# PIC32_Subsystem.net
KiCad netlist of a schematic drawn in Altium Designer
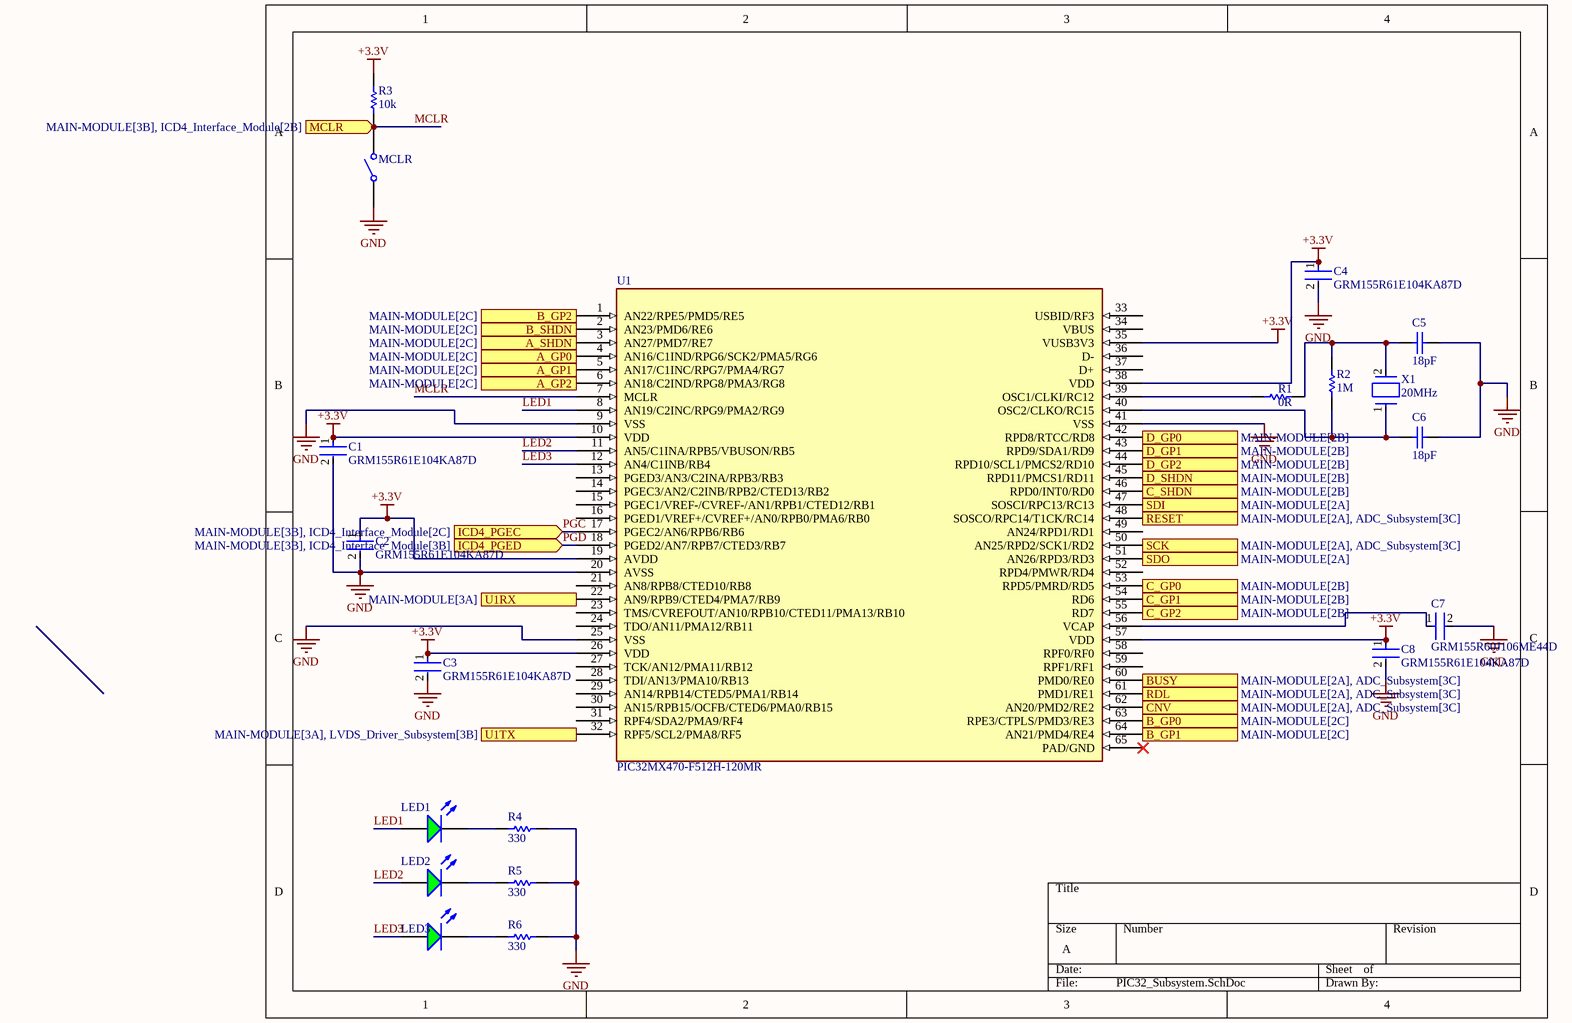
[diagram p0: PIC32_Subsystem.SchDoc]

(export (version "E")
  (design (tool "Eeschema 10.0.6"))
  (components
    (comp (ref "C1")
      (value "GRM155R61E104KA87D")
      (footprint "FP-GRM155-0_05-IPC_A")
      (description "CAP CER 0.1UF 25V X5R 0402")
      (fields (field (name "VOLTAGE") "25V") (field (name "TOLERANCE") "10%"))
      (libsource (lib "Altium Content Vault") (part "11868f565c42a9108669ba33697ecf6"))
    )
    (comp (ref "C2")
      (value "GRM155R61E104KA87D")
      (footprint "FP-GRM155-0_05-IPC_A")
      (description "CAP CER 0.1UF 25V X5R 0402")
      (fields (field (name "VOLTAGE") "25V") (field (name "TOLERANCE") "10%"))
      (libsource (lib "Altium Content Vault") (part "11868f565c42a9108669ba33697ecf6"))
    )
    (comp (ref "C3")
      (value "GRM155R61E104KA87D")
      (footprint "FP-GRM155-0_05-IPC_A")
      (description "CAP CER 0.1UF 25V X5R 0402")
      (fields (field (name "VOLTAGE") "25V") (field (name "TOLERANCE") "10%"))
      (libsource (lib "Altium Content Vault") (part "11868f565c42a9108669ba33697ecf6"))
    )
    (comp (ref "C4")
      (value "GRM155R61E104KA87D")
      (footprint "FP-GRM155-0_05-IPC_A")
      (description "CAP CER 0.1UF 25V X5R 0402")
      (fields (field (name "VOLTAGE") "25V") (field (name "TOLERANCE") "10%"))
      (libsource (lib "Altium Content Vault") (part "11868f565c42a9108669ba33697ecf6"))
    )
    (comp (ref "C5")
      (value "18pF")
      (footprint "CAPC1005X55X25LL05T10")
      (description "GRM1555C1H180GA01D")
      (fields (field (name "MANUFACTURER") "Murata"))
      (libsource (lib "Altium Content Vault") (part "CAP"))
    )
    (comp (ref "C6")
      (value "18pF")
      (footprint "CAPC1005X55X25LL05T10")
      (description "GRM1555C1H180GA01D")
      (fields (field (name "MANUFACTURER") "Murata"))
      (libsource (lib "Altium Content Vault") (part "CAP"))
    )
    (comp (ref "C7")
      (value "GRM155R60J106ME44D")
      (footprint "FP-GRM155-0_2-IPC_A")
      (description "CAP CER 10UF 6.3V X5R 0402")
      (fields (field (name "VOLTAGE") "6.3V") (field (name "TOLERANCE") "20%"))
      (libsource (lib "Altium Content Vault") (part "b4654b650e69147ec39a6b967a45e02"))
    )
    (comp (ref "C8")
      (value "GRM155R61E104KA87D")
      (footprint "FP-GRM155-0_05-IPC_A")
      (description "CAP CER 0.1UF 25V X5R 0402")
      (fields (field (name "VOLTAGE") "25V") (field (name "TOLERANCE") "10%"))
      (libsource (lib "Altium Content Vault") (part "11868f565c42a9108669ba33697ecf6"))
    )
    (comp (ref "LED1")
      (value "~")
      (footprint "KING-APT1608SGC_V")
      (description "Super Bright Green LED, 62.5 mW, 25 mA, -40 to 85 degC, 2-Pin SMD, RoHS, Tape and Reel, APT1608SGC")
      (fields (field (name "MANUFACTURER") "Kingbright"))
      (libsource (lib "Altium Content Vault") (part "LED-GREEN-AK-2"))
    )
    (comp (ref "LED2")
      (value "~")
      (footprint "KING-APT1608SGC_V")
      (description "Super Bright Green LED, 62.5 mW, 25 mA, -40 to 85 degC, 2-Pin SMD, RoHS, Tape and Reel, APT1608SGC")
      (fields (field (name "MANUFACTURER") "Kingbright"))
      (libsource (lib "Altium Content Vault") (part "LED-GREEN-AK-2"))
    )
    (comp (ref "LED3")
      (value "~")
      (footprint "KING-APT1608SGC_V")
      (description "Super Bright Green LED, 62.5 mW, 25 mA, -40 to 85 degC, 2-Pin SMD, RoHS, Tape and Reel, APT1608SGC")
      (fields (field (name "MANUFACTURER") "Kingbright"))
      (libsource (lib "Altium Content Vault") (part "LED-GREEN-AK-2"))
    )
    (comp (ref "MCLR")
      (value "434121043816")
      (footprint "434121043816")
      (description "WS-TASV SMD Tact Switch 6.0X3.5 mm")
      (fields (field (name "MANUFACTURER") "Wuerth Elektronik"))
      (libsource (lib "Altium Content Vault") (part "WE-TACT-SW-2"))
    )
    (comp (ref "R1")
      (value "0R")
      (footprint "RESC1005X40X25LL05T10")
      (description "RC0402JR-070RL")
      (fields (field (name "MANUFACTURER") "Yageo / Phycomp"))
      (libsource (lib "Altium Content Vault") (part "RES"))
    )
    (comp (ref "R2")
      (value "1M")
      (footprint "RESC1005X40X25LL05T05")
      (fields
        (field (name "PARTNUMBER") "ERJ-2RKF1004X")
        (field (name "TOLERANCE") "1%")
        (field (name "MANUFACTURER") "Basic Passives")
      )
      (libsource (lib "Altium Content Vault") (part "RES-2"))
    )
    (comp (ref "R3")
      (value "10k")
      (footprint "RESC1005X40X25LL05T05")
      (fields (field (name "TOLERANCE") "1%") (field (name "MANUFACTURER") "Panasonic"))
      (libsource (lib "Altium Content Vault") (part "RES-2"))
    )
    (comp (ref "R4")
      (value "330")
      (footprint "RESC1609X50X30LL10T20")
      (description "CRCW0603330RJNEA")
      (fields (field (name "MANUFACTURER") "Vishay Dale"))
      (libsource (lib "Altium Content Vault") (part "RES"))
    )
    (comp (ref "R5")
      (value "330")
      (footprint "RESC1609X50X30LL10T20")
      (description "CRCW0603330RJNEA")
      (fields (field (name "MANUFACTURER") "Vishay Dale"))
      (libsource (lib "Altium Content Vault") (part "RES"))
    )
    (comp (ref "R6")
      (value "330")
      (footprint "RESC1609X50X30LL10T20")
      (description "CRCW0603330RJNEA")
      (fields (field (name "MANUFACTURER") "Vishay Dale"))
      (libsource (lib "Altium Content Vault") (part "RES"))
    )
    (comp (ref "U1")
      (value "PIC32MX470-F512H-120MR")
      (footprint "TQFP")
      (libsource (lib "PIC32MX470-F512H-120MR") (part "PIC32MX470-F512H-120MR"))
    )
    (comp (ref "X1")
      (value "20MHz")
      (footprint "FP-ABM7-MFG")
      (description "Crystal 20MHz ±20ppm 18pF SMD-2 6mm x 3.5mm\r\nABM7-20.000MHZ-D2Y-T")
      (fields (field (name "TOLERANCE") "20ppm"))
      (libsource (lib "Altium Content Vault") (part "c23a69dc6c9e2f18f2079038eb95dd1"))
    )
  )
  (nets
    (net (code "1") (name "+3.3V") (class "Default")
      (node (ref "C1") (pin "1") (pinfunction "1_1") (pintype "passive"))
      (node (ref "C2") (pin "1") (pinfunction "1_1") (pintype "passive"))
      (node (ref "C3") (pin "1") (pinfunction "1_1") (pintype "passive"))
      (node (ref "C4") (pin "1") (pinfunction "1_1") (pintype "passive"))
      (node (ref "C8") (pin "1") (pinfunction "1_1") (pintype "passive"))
      (node (ref "R3") (pin "2") (pinfunction "2_2") (pintype "passive"))
      (node (ref "U1") (pin "10") (pinfunction "VDD_10") (pintype "input"))
      (node (ref "U1") (pin "19") (pinfunction "AVDD_19") (pintype "input"))
      (node (ref "U1") (pin "26") (pinfunction "VDD_26") (pintype "input"))
      (node (ref "U1") (pin "35") (pinfunction "VUSB3V3_35") (pintype "input"))
      (node (ref "U1") (pin "38") (pinfunction "VDD_38") (pintype "input"))
      (node (ref "U1") (pin "57") (pinfunction "VDD_57") (pintype "input"))
    )
    (net (code "2") (name "/A_GP0") (class "Default")
      (node (ref "U1") (pin "4") (pinfunction "AN16/C1IND/RPG6/SCK2/PMA5/RG6_4") (pintype "input"))
    )
    (net (code "3") (name "/A_GP1") (class "Default")
      (node (ref "U1") (pin "5") (pinfunction "AN17/C1INC/RPG7/PMA4/RG7_5") (pintype "input"))
    )
    (net (code "4") (name "/A_GP2") (class "Default")
      (node (ref "U1") (pin "6") (pinfunction "AN18/C2IND/RPG8/PMA3/RG8_6") (pintype "input"))
    )
    (net (code "5") (name "/A_SHDN") (class "Default")
      (node (ref "U1") (pin "3") (pinfunction "AN27/PMD7/RE7_3") (pintype "input"))
    )
    (net (code "6") (name "/BUSY") (class "Default")
      (node (ref "U1") (pin "60") (pinfunction "PMD0/RE0_60") (pintype "input"))
    )
    (net (code "7") (name "/B_GP0") (class "Default")
      (node (ref "U1") (pin "63") (pinfunction "RPE3/CTPLS/PMD3/RE3_63") (pintype "input"))
    )
    (net (code "8") (name "/B_GP1") (class "Default")
      (node (ref "U1") (pin "64") (pinfunction "AN21/PMD4/RE4_64") (pintype "input"))
    )
    (net (code "9") (name "/B_GP2") (class "Default")
      (node (ref "U1") (pin "1") (pinfunction "AN22/RPE5/PMD5/RE5_1") (pintype "input"))
    )
    (net (code "10") (name "/B_SHDN") (class "Default")
      (node (ref "U1") (pin "2") (pinfunction "AN23/PMD6/RE6_2") (pintype "input"))
    )
    (net (code "11") (name "/CNV") (class "Default")
      (node (ref "U1") (pin "62") (pinfunction "AN20/PMD2/RE2_62") (pintype "input"))
    )
    (net (code "12") (name "/C_GP0") (class "Default")
      (node (ref "U1") (pin "53") (pinfunction "RPD5/PMRD/RD5_53") (pintype "input"))
    )
    (net (code "13") (name "/C_GP1") (class "Default")
      (node (ref "U1") (pin "54") (pinfunction "RD6_54") (pintype "input"))
    )
    (net (code "14") (name "/C_GP2") (class "Default")
      (node (ref "U1") (pin "55") (pinfunction "RD7_55") (pintype "input"))
    )
    (net (code "15") (name "/C_SHDN") (class "Default")
      (node (ref "U1") (pin "46") (pinfunction "RPD0/INT0/RD0_46") (pintype "input"))
    )
    (net (code "16") (name "/D_GP0") (class "Default")
      (node (ref "U1") (pin "42") (pinfunction "RPD8/RTCC/RD8_42") (pintype "input"))
    )
    (net (code "17") (name "/D_GP1") (class "Default")
      (node (ref "U1") (pin "43") (pinfunction "RPD9/SDA1/RD9_43") (pintype "input"))
    )
    (net (code "18") (name "/D_GP2") (class "Default")
      (node (ref "U1") (pin "44") (pinfunction "RPD10/SCL1/PMCS2/RD10_44") (pintype "input"))
    )
    (net (code "19") (name "/D_SHDN") (class "Default")
      (node (ref "U1") (pin "45") (pinfunction "RPD11/PMCS1/RD11_45") (pintype "input"))
    )
    (net (code "20") (name "/LED1") (class "Default")
      (node (ref "LED1") (pin "1") (pinfunction "A_1") (pintype "passive"))
      (node (ref "U1") (pin "8") (pinfunction "AN19/C2INC/RPG9/PMA2/RG9_8") (pintype "input"))
    )
    (net (code "21") (name "/LED2") (class "Default")
      (node (ref "LED2") (pin "1") (pinfunction "A_1") (pintype "passive"))
      (node (ref "U1") (pin "11") (pinfunction "AN5/C1INA/RPB5/VBUSON/RB5_11") (pintype "input"))
    )
    (net (code "22") (name "/LED3") (class "Default")
      (node (ref "LED3") (pin "1") (pinfunction "A_1") (pintype "passive"))
      (node (ref "U1") (pin "12") (pinfunction "AN4/C1INB/RB4_12") (pintype "input"))
    )
    (net (code "23") (name "/MCLR") (class "Default")
      (node (ref "MCLR") (pin "2") (pinfunction "2_2") (pintype "passive"))
      (node (ref "R3") (pin "1") (pinfunction "1_1") (pintype "passive"))
      (node (ref "U1") (pin "7") (pinfunction "MCLR_7") (pintype "input"))
    )
    (net (code "24") (name "/PGC") (class "Default")
      (node (ref "U1") (pin "17") (pinfunction "PGEC2/AN6/RPB6/RB6_17") (pintype "input"))
    )
    (net (code "25") (name "/PGD") (class "Default")
      (node (ref "U1") (pin "18") (pinfunction "PGED2/AN7/RPB7/CTED3/RB7_18") (pintype "input"))
    )
    (net (code "26") (name "/RDL") (class "Default")
      (node (ref "U1") (pin "61") (pinfunction "PMD1/RE1_61") (pintype "input"))
    )
    (net (code "27") (name "/RESET") (class "Default")
      (node (ref "U1") (pin "48") (pinfunction "SOSCO/RPC14/T1CK/RC14_48") (pintype "input"))
    )
    (net (code "28") (name "/SCK") (class "Default")
      (node (ref "U1") (pin "50") (pinfunction "AN25/RPD2/SCK1/RD2_50") (pintype "input"))
    )
    (net (code "29") (name "/SDI") (class "Default")
      (node (ref "U1") (pin "47") (pinfunction "SOSCI/RPC13/RC13_47") (pintype "input"))
    )
    (net (code "30") (name "/SDO") (class "Default")
      (node (ref "U1") (pin "51") (pinfunction "AN26/RPD3/RD3_51") (pintype "input"))
    )
    (net (code "31") (name "/U1RX") (class "Default")
      (node (ref "U1") (pin "22") (pinfunction "AN9/RPB9/CTED4/PMA7/RB9_22") (pintype "input"))
    )
    (net (code "32") (name "/U1TX") (class "Default")
      (node (ref "U1") (pin "32") (pinfunction "RPF5/SCL2/PMA8/RF5_32") (pintype "input"))
    )
    (net (code "33") (name "GND") (class "Default")
      (node (ref "C1") (pin "2") (pinfunction "2_2") (pintype "passive"))
      (node (ref "C2") (pin "2") (pinfunction "2_2") (pintype "passive"))
      (node (ref "C3") (pin "2") (pinfunction "2_2") (pintype "passive"))
      (node (ref "C4") (pin "2") (pinfunction "2_2") (pintype "passive"))
      (node (ref "C5") (pin "2") (pinfunction "2_2") (pintype "passive"))
      (node (ref "C6") (pin "2") (pinfunction "2_2") (pintype "passive"))
      (node (ref "C7") (pin "2") (pinfunction "2_2") (pintype "passive"))
      (node (ref "C8") (pin "2") (pinfunction "2_2") (pintype "passive"))
      (node (ref "MCLR") (pin "1") (pinfunction "1_1") (pintype "passive"))
      (node (ref "R4") (pin "2") (pinfunction "2_2") (pintype "passive"))
      (node (ref "R5") (pin "2") (pinfunction "2_2") (pintype "passive"))
      (node (ref "R6") (pin "2") (pinfunction "2_2") (pintype "passive"))
      (node (ref "U1") (pin "20") (pinfunction "AVSS_20") (pintype "input"))
      (node (ref "U1") (pin "25") (pinfunction "VSS_25") (pintype "input"))
      (node (ref "U1") (pin "41") (pinfunction "VSS_41") (pintype "input"))
      (node (ref "U1") (pin "9") (pinfunction "VSS_9") (pintype "input"))
    )
    (net (code "34") (name "Net-(C5-Pad1)") (class "Default")
      (node (ref "C5") (pin "1") (pinfunction "1_1") (pintype "passive"))
      (node (ref "R1") (pin "2") (pinfunction "2_2") (pintype "passive"))
      (node (ref "R2") (pin "2") (pinfunction "2_2") (pintype "passive"))
      (node (ref "X1") (pin "2") (pinfunction "2_2") (pintype "passive"))
    )
    (net (code "35") (name "Net-(LED1-K)") (class "Default")
      (node (ref "LED1") (pin "2") (pinfunction "K_2") (pintype "passive"))
      (node (ref "R4") (pin "1") (pinfunction "1_1") (pintype "passive"))
    )
    (net (code "36") (name "Net-(LED2-K)") (class "Default")
      (node (ref "LED2") (pin "2") (pinfunction "K_2") (pintype "passive"))
      (node (ref "R5") (pin "1") (pinfunction "1_1") (pintype "passive"))
    )
    (net (code "37") (name "Net-(LED3-K)") (class "Default")
      (node (ref "LED3") (pin "2") (pinfunction "K_2") (pintype "passive"))
      (node (ref "R6") (pin "1") (pinfunction "1_1") (pintype "passive"))
    )
    (net (code "38") (name "Net-(U1-OSC1{slash}CLKI{slash}RC12)") (class "Default")
      (node (ref "R1") (pin "1") (pinfunction "1_1") (pintype "passive"))
      (node (ref "U1") (pin "39") (pinfunction "OSC1/CLKI/RC12_39") (pintype "input"))
    )
    (net (code "39") (name "Net-(U1-OSC2{slash}CLKO{slash}RC15)") (class "Default")
      (node (ref "C6") (pin "1") (pinfunction "1_1") (pintype "passive"))
      (node (ref "R2") (pin "1") (pinfunction "1_1") (pintype "passive"))
      (node (ref "U1") (pin "40") (pinfunction "OSC2/CLKO/RC15_40") (pintype "input"))
      (node (ref "X1") (pin "1") (pinfunction "1_1") (pintype "passive"))
    )
    (net (code "40") (name "Net-(U1-VCAP)") (class "Default")
      (node (ref "C7") (pin "1") (pinfunction "1_1") (pintype "passive"))
      (node (ref "U1") (pin "56") (pinfunction "VCAP_56") (pintype "input"))
    )
    (net (code "41") (name "unconnected-(U1-AN8{slash}RPB8{slash}CTED10{slash}RB8-Pad21)") (class "Default")
      (node (ref "U1") (pin "21") (pinfunction "AN8/RPB8/CTED10/RB8_21") (pintype "input"))
    )
    (net (code "42") (name "unconnected-(U1-AN14{slash}RPB14{slash}CTED5{slash}PMA1{slash}RB14-Pad29)") (class "Default")
      (node (ref "U1") (pin "29") (pinfunction "AN14/RPB14/CTED5/PMA1/RB14_29") (pintype "input"))
    )
    (net (code "43") (name "unconnected-(U1-AN15{slash}RPB15{slash}OCFB{slash}CTED6{slash}PMA0{slash}RB15-Pad30)") (class "Default")
      (node (ref "U1") (pin "30") (pinfunction "AN15/RPB15/OCFB/CTED6/PMA0/RB15_30") (pintype "input"))
    )
    (net (code "44") (name "unconnected-(U1-AN24{slash}RPD1{slash}RD1-Pad49)") (class "Default")
      (node (ref "U1") (pin "49") (pinfunction "AN24/RPD1/RD1_49") (pintype "input"))
    )
    (net (code "45") (name "unconnected-(U1-D+-Pad37)") (class "Default")
      (node (ref "U1") (pin "37") (pinfunction "D+_37") (pintype "input"))
    )
    (net (code "46") (name "unconnected-(U1-D--Pad36)") (class "Default")
      (node (ref "U1") (pin "36") (pinfunction "D-_36") (pintype "input"))
    )
    (net (code "47") (name "unconnected-(U1-PAD{slash}GND-Pad65)") (class "Default")
      (node (ref "U1") (pin "65") (pinfunction "PAD/GND_65") (pintype "input+no_connect"))
    )
    (net (code "48") (name "unconnected-(U1-PGEC1{slash}VREF-{slash}CVREF-{slash}AN1{slash}RPB1{slash}CTED12{slash}RB1-Pad15)") (class "Default")
      (node (ref "U1") (pin "15") (pinfunction "PGEC1/VREF-/CVREF-/AN1/RPB1/CTED12/RB1_15") (pintype "input"))
    )
    (net (code "49") (name "unconnected-(U1-PGEC3{slash}AN2{slash}C2INB{slash}RPB2{slash}CTED13{slash}RB2-Pad14)") (class "Default")
      (node (ref "U1") (pin "14") (pinfunction "PGEC3/AN2/C2INB/RPB2/CTED13/RB2_14") (pintype "input"))
    )
    (net (code "50") (name "unconnected-(U1-PGED1{slash}VREF+{slash}CVREF+{slash}AN0{slash}RPB0{slash}PMA6{slash}RB0-Pad16)") (class "Default")
      (node (ref "U1") (pin "16") (pinfunction "PGED1/VREF+/CVREF+/AN0/RPB0/PMA6/RB0_16") (pintype "input"))
    )
    (net (code "51") (name "unconnected-(U1-PGED3{slash}AN3{slash}C2INA{slash}RPB3{slash}RB3-Pad13)") (class "Default")
      (node (ref "U1") (pin "13") (pinfunction "PGED3/AN3/C2INA/RPB3/RB3_13") (pintype "input"))
    )
    (net (code "52") (name "unconnected-(U1-RPD4{slash}PMWR{slash}RD4-Pad52)") (class "Default")
      (node (ref "U1") (pin "52") (pinfunction "RPD4/PMWR/RD4_52") (pintype "input"))
    )
    (net (code "53") (name "unconnected-(U1-RPF0{slash}RF0-Pad58)") (class "Default")
      (node (ref "U1") (pin "58") (pinfunction "RPF0/RF0_58") (pintype "input"))
    )
    (net (code "54") (name "unconnected-(U1-RPF1{slash}RF1-Pad59)") (class "Default")
      (node (ref "U1") (pin "59") (pinfunction "RPF1/RF1_59") (pintype "input"))
    )
    (net (code "55") (name "unconnected-(U1-RPF4{slash}SDA2{slash}PMA9{slash}RF4-Pad31)") (class "Default")
      (node (ref "U1") (pin "31") (pinfunction "RPF4/SDA2/PMA9/RF4_31") (pintype "input"))
    )
    (net (code "56") (name "unconnected-(U1-TCK{slash}AN12{slash}PMA11{slash}RB12-Pad27)") (class "Default")
      (node (ref "U1") (pin "27") (pinfunction "TCK/AN12/PMA11/RB12_27") (pintype "input"))
    )
    (net (code "57") (name "unconnected-(U1-TDI{slash}AN13{slash}PMA10{slash}RB13-Pad28)") (class "Default")
      (node (ref "U1") (pin "28") (pinfunction "TDI/AN13/PMA10/RB13_28") (pintype "input"))
    )
    (net (code "58") (name "unconnected-(U1-TDO{slash}AN11{slash}PMA12{slash}RB11-Pad24)") (class "Default")
      (node (ref "U1") (pin "24") (pinfunction "TDO/AN11/PMA12/RB11_24") (pintype "input"))
    )
    (net (code "59") (name "unconnected-(U1-TMS{slash}CVREFOUT{slash}AN10{slash}RPB10{slash}CTED11{slash}PMA13{slash}RB10-Pad23)") (class "Default")
      (node (ref "U1") (pin "23") (pinfunction "TMS/CVREFOUT/AN10/RPB10/CTED11/PMA13/RB10_23") (pintype "input"))
    )
    (net (code "60") (name "unconnected-(U1-USBID{slash}RF3-Pad33)") (class "Default")
      (node (ref "U1") (pin "33") (pinfunction "USBID/RF3_33") (pintype "input"))
    )
    (net (code "61") (name "unconnected-(U1-VBUS-Pad34)") (class "Default")
      (node (ref "U1") (pin "34") (pinfunction "VBUS_34") (pintype "input"))
    )
  )
)
